# Si5395_CLK_GEN.net
KiCad netlist of a schematic drawn in Altium Designer
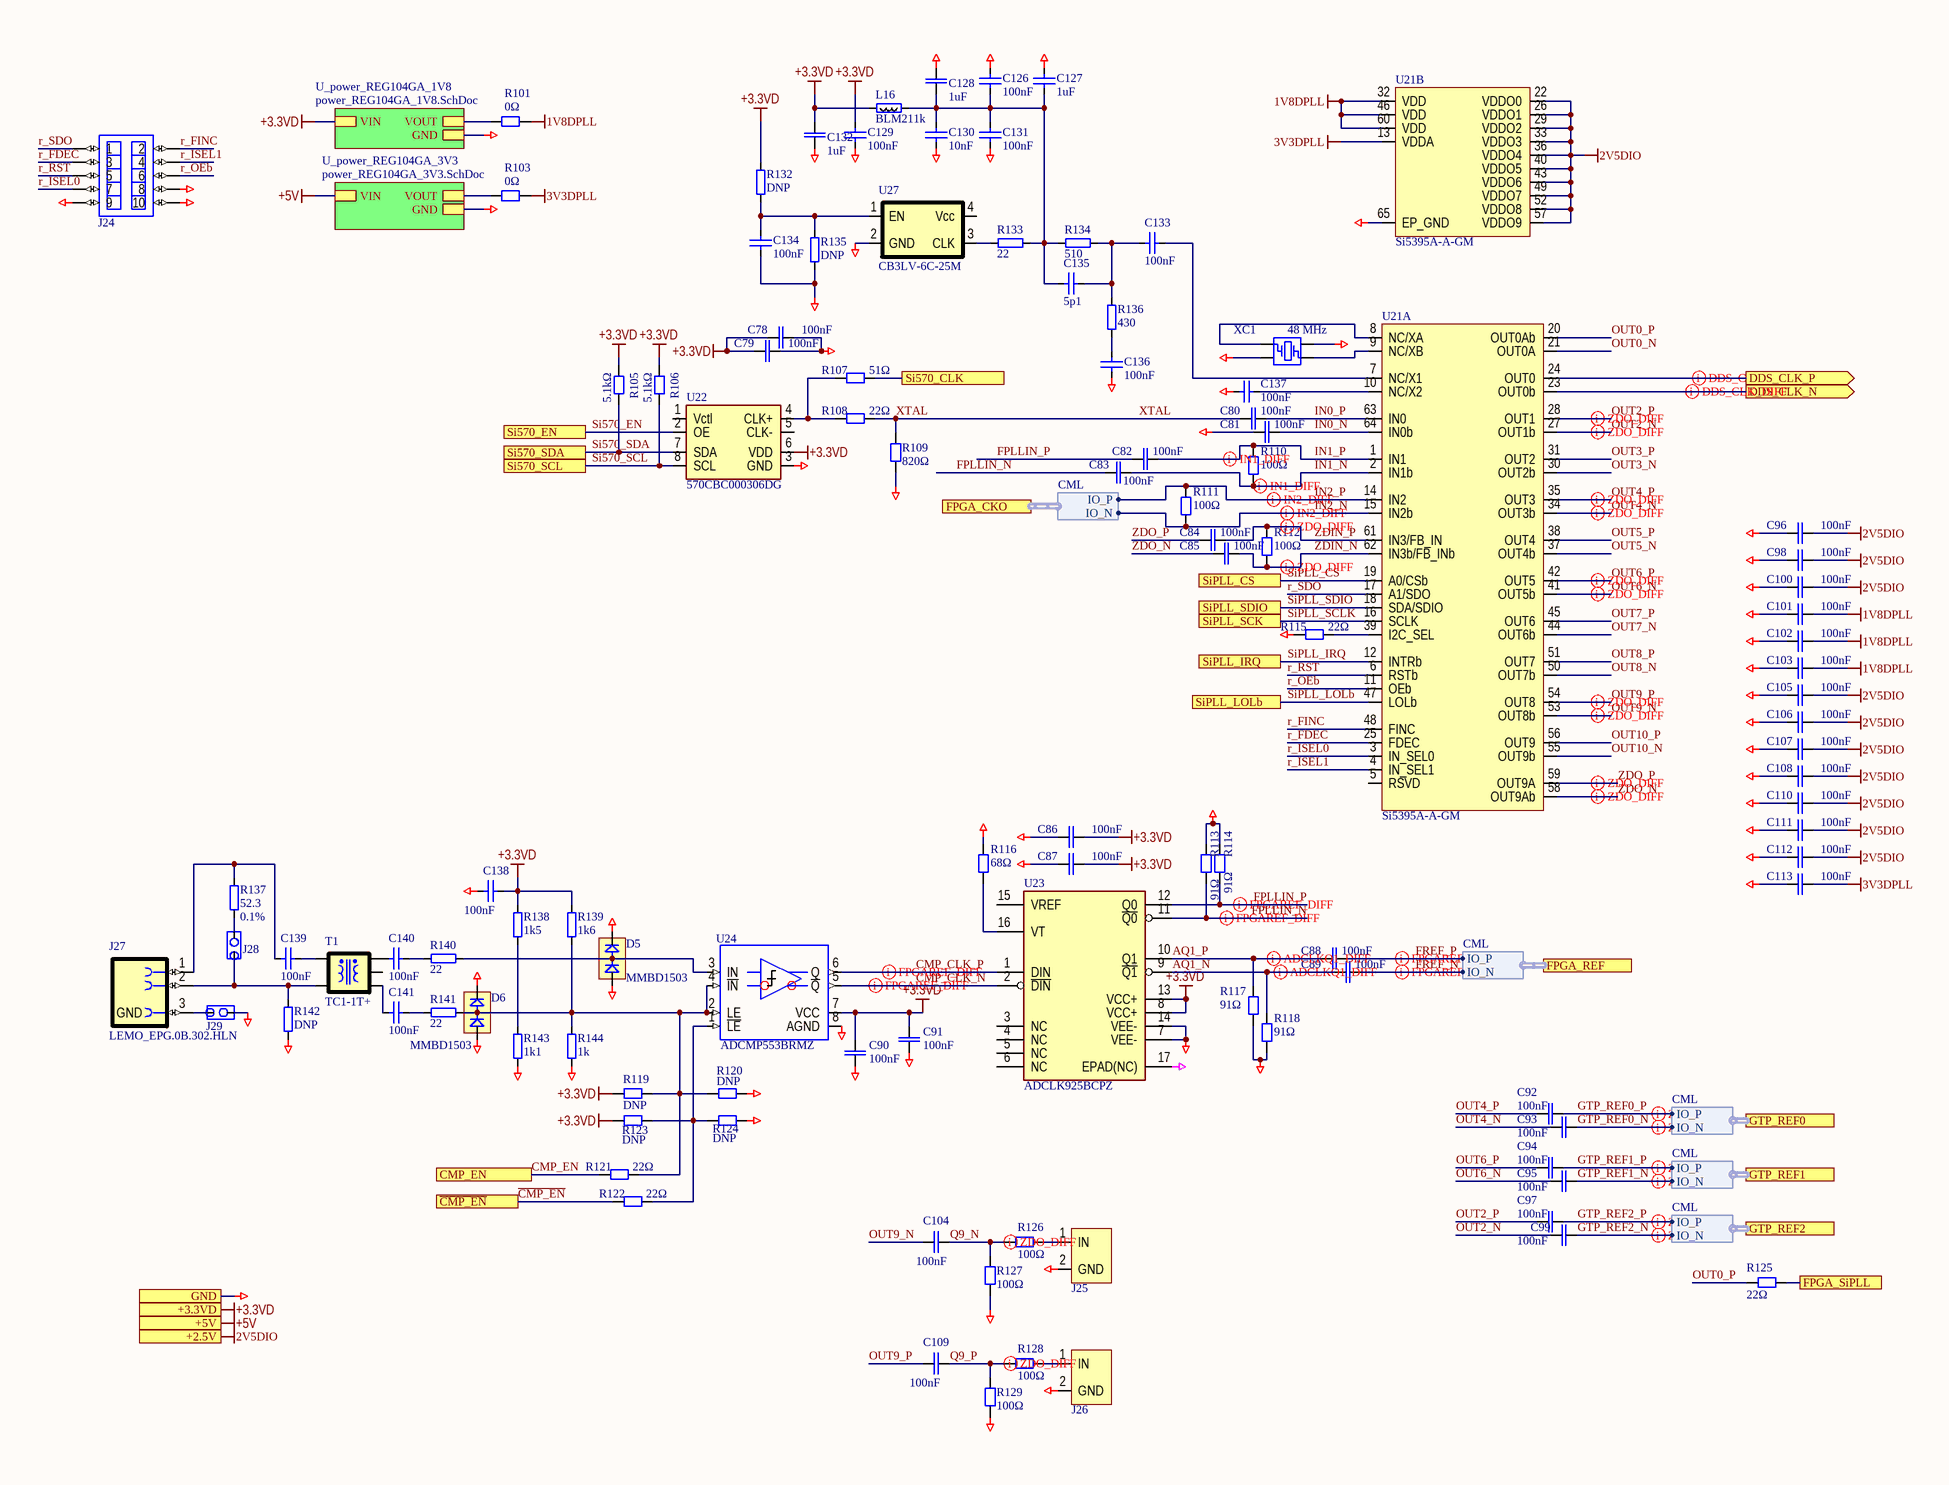
[diagram p0: Si5395_CLK_GEN.SchDoc]

(export (version "E")
  (design (tool "Eeschema 10.0.6"))
  (components
    (comp (ref "C78")
      (value "100nF")
      (footprint "CAPC1608N")
      (description "Generic ceramic SMD capacitor")
      (fields (field (name "MAINTAINER") "Evgeniy Kotov"))
      (libsource (lib "carrier") (part "CAPC"))
    )
    (comp (ref "C79")
      (value "100nF")
      (footprint "CAPC1608N")
      (description "Generic ceramic SMD capacitor")
      (fields (field (name "MAINTAINER") "Evgeniy Kotov"))
      (libsource (lib "carrier") (part "CAPC"))
    )
    (comp (ref "C80")
      (value "100nF")
      (footprint "CAPC1608N")
      (description "Generic ceramic SMD capacitor")
      (fields (field (name "MAINTAINER") "Evgeniy Kotov"))
      (libsource (lib "carrier") (part "CAPC"))
    )
    (comp (ref "C81")
      (value "100nF")
      (footprint "CAPC1608N")
      (description "Generic ceramic SMD capacitor")
      (fields (field (name "MAINTAINER") "Evgeniy Kotov"))
      (libsource (lib "carrier") (part "CAPC"))
    )
    (comp (ref "C82")
      (value "100nF")
      (footprint "CAPC1608N")
      (description "Generic ceramic SMD capacitor")
      (fields (field (name "MAINTAINER") "Evgeniy Kotov"))
      (libsource (lib "carrier") (part "CAPC"))
    )
    (comp (ref "C83")
      (value "100nF")
      (footprint "CAPC1608N")
      (description "Generic ceramic SMD capacitor")
      (fields (field (name "MAINTAINER") "Evgeniy Kotov"))
      (libsource (lib "carrier") (part "CAPC"))
    )
    (comp (ref "C84")
      (value "100nF")
      (footprint "CAPC1608N")
      (description "Generic ceramic SMD capacitor")
      (fields (field (name "MAINTAINER") "Evgeniy Kotov"))
      (libsource (lib "carrier") (part "CAPC"))
    )
    (comp (ref "C85")
      (value "100nF")
      (footprint "CAPC1608N")
      (description "Generic ceramic SMD capacitor")
      (fields (field (name "MAINTAINER") "Evgeniy Kotov"))
      (libsource (lib "carrier") (part "CAPC"))
    )
    (comp (ref "C86")
      (value "100nF")
      (footprint "CAPC1608N")
      (description "Generic ceramic SMD capacitor")
      (fields (field (name "MAINTAINER") "Evgeniy Kotov"))
      (libsource (lib "carrier") (part "CAPC"))
    )
    (comp (ref "C87")
      (value "100nF")
      (footprint "CAPC1608N")
      (description "Generic ceramic SMD capacitor")
      (fields (field (name "MAINTAINER") "Evgeniy Kotov"))
      (libsource (lib "carrier") (part "CAPC"))
    )
    (comp (ref "C88")
      (value "100nF")
      (footprint "CAPC1608N")
      (description "Generic ceramic SMD capacitor")
      (fields (field (name "MAINTAINER") "Evgeniy Kotov"))
      (libsource (lib "carrier") (part "CAPC"))
    )
    (comp (ref "C89")
      (value "100nF")
      (footprint "CAPC1608N")
      (description "Generic ceramic SMD capacitor")
      (fields (field (name "MAINTAINER") "Evgeniy Kotov"))
      (libsource (lib "carrier") (part "CAPC"))
    )
    (comp (ref "C90")
      (value "100nF")
      (footprint "CAPC1608N")
      (description "Generic ceramic SMD capacitor")
      (fields (field (name "MAINTAINER") "Evgeniy Kotov"))
      (libsource (lib "carrier") (part "CAPC"))
    )
    (comp (ref "C91")
      (value "100nF")
      (footprint "CAPC1608N")
      (description "Generic ceramic SMD capacitor")
      (fields (field (name "MAINTAINER") "Evgeniy Kotov"))
      (libsource (lib "carrier") (part "CAPC"))
    )
    (comp (ref "C92")
      (value "100nF")
      (footprint "CAPC1608N")
      (description "Generic ceramic SMD capacitor")
      (fields (field (name "MAINTAINER") "Evgeniy Kotov"))
      (libsource (lib "carrier") (part "CAPC"))
    )
    (comp (ref "C93")
      (value "100nF")
      (footprint "CAPC1608N")
      (description "Generic ceramic SMD capacitor")
      (fields (field (name "MAINTAINER") "Evgeniy Kotov"))
      (libsource (lib "carrier") (part "CAPC"))
    )
    (comp (ref "C94")
      (value "100nF")
      (footprint "CAPC1608N")
      (description "Generic ceramic SMD capacitor")
      (fields (field (name "MAINTAINER") "Evgeniy Kotov"))
      (libsource (lib "carrier") (part "CAPC"))
    )
    (comp (ref "C95")
      (value "100nF")
      (footprint "CAPC1608N")
      (description "Generic ceramic SMD capacitor")
      (fields (field (name "MAINTAINER") "Evgeniy Kotov"))
      (libsource (lib "carrier") (part "CAPC"))
    )
    (comp (ref "C96")
      (value "100nF")
      (footprint "CAPC1608N")
      (description "Generic ceramic SMD capacitor")
      (fields (field (name "MAINTAINER") "Evgeniy Kotov"))
      (libsource (lib "carrier") (part "CAPC"))
    )
    (comp (ref "C97")
      (value "100nF")
      (footprint "CAPC1608N")
      (description "Generic ceramic SMD capacitor")
      (fields (field (name "MAINTAINER") "Evgeniy Kotov"))
      (libsource (lib "carrier") (part "CAPC"))
    )
    (comp (ref "C98")
      (value "100nF")
      (footprint "CAPC1608N")
      (description "Generic ceramic SMD capacitor")
      (fields (field (name "MAINTAINER") "Evgeniy Kotov"))
      (libsource (lib "carrier") (part "CAPC"))
    )
    (comp (ref "C99")
      (value "100nF")
      (footprint "CAPC1608N")
      (description "Generic ceramic SMD capacitor")
      (fields (field (name "MAINTAINER") "Evgeniy Kotov"))
      (libsource (lib "carrier") (part "CAPC"))
    )
    (comp (ref "C100")
      (value "100nF")
      (footprint "CAPC1608N")
      (description "Generic ceramic SMD capacitor")
      (fields (field (name "MAINTAINER") "Evgeniy Kotov"))
      (libsource (lib "carrier") (part "CAPC"))
    )
    (comp (ref "C101")
      (value "100nF")
      (footprint "CAPC1608N")
      (description "Generic ceramic SMD capacitor")
      (fields (field (name "MAINTAINER") "Evgeniy Kotov"))
      (libsource (lib "carrier") (part "CAPC"))
    )
    (comp (ref "C102")
      (value "100nF")
      (footprint "CAPC1608N")
      (description "Generic ceramic SMD capacitor")
      (fields (field (name "MAINTAINER") "Evgeniy Kotov"))
      (libsource (lib "carrier") (part "CAPC"))
    )
    (comp (ref "C103")
      (value "100nF")
      (footprint "CAPC1608N")
      (description "Generic ceramic SMD capacitor")
      (fields (field (name "MAINTAINER") "Evgeniy Kotov"))
      (libsource (lib "carrier") (part "CAPC"))
    )
    (comp (ref "C104")
      (value "100nF")
      (footprint "CAPC1608N")
      (description "Generic ceramic SMD capacitor")
      (fields (field (name "MAINTAINER") "Evgeniy Kotov"))
      (libsource (lib "carrier") (part "CAPC"))
    )
    (comp (ref "C105")
      (value "100nF")
      (footprint "CAPC1608N")
      (description "Generic ceramic SMD capacitor")
      (fields (field (name "MAINTAINER") "Evgeniy Kotov"))
      (libsource (lib "carrier") (part "CAPC"))
    )
    (comp (ref "C106")
      (value "100nF")
      (footprint "CAPC1608N")
      (description "Generic ceramic SMD capacitor")
      (fields (field (name "MAINTAINER") "Evgeniy Kotov"))
      (libsource (lib "carrier") (part "CAPC"))
    )
    (comp (ref "C107")
      (value "100nF")
      (footprint "CAPC1608N")
      (description "Generic ceramic SMD capacitor")
      (fields (field (name "MAINTAINER") "Evgeniy Kotov"))
      (libsource (lib "carrier") (part "CAPC"))
    )
    (comp (ref "C108")
      (value "100nF")
      (footprint "CAPC1608N")
      (description "Generic ceramic SMD capacitor")
      (fields (field (name "MAINTAINER") "Evgeniy Kotov"))
      (libsource (lib "carrier") (part "CAPC"))
    )
    (comp (ref "C109")
      (value "100nF")
      (footprint "CAPC1608N")
      (description "Generic ceramic SMD capacitor")
      (fields (field (name "MAINTAINER") "Evgeniy Kotov"))
      (libsource (lib "carrier") (part "CAPC"))
    )
    (comp (ref "C110")
      (value "100nF")
      (footprint "CAPC1608N")
      (description "Generic ceramic SMD capacitor")
      (fields (field (name "MAINTAINER") "Evgeniy Kotov"))
      (libsource (lib "carrier") (part "CAPC"))
    )
    (comp (ref "C111")
      (value "100nF")
      (footprint "CAPC1608N")
      (description "Generic ceramic SMD capacitor")
      (fields (field (name "MAINTAINER") "Evgeniy Kotov"))
      (libsource (lib "carrier") (part "CAPC"))
    )
    (comp (ref "C112")
      (value "100nF")
      (footprint "CAPC1608N")
      (description "Generic ceramic SMD capacitor")
      (fields (field (name "MAINTAINER") "Evgeniy Kotov"))
      (libsource (lib "carrier") (part "CAPC"))
    )
    (comp (ref "C113")
      (value "100nF")
      (footprint "CAPC1608N")
      (description "Generic ceramic SMD capacitor")
      (fields (field (name "MAINTAINER") "Evgeniy Kotov"))
      (libsource (lib "carrier") (part "CAPC"))
    )
    (comp (ref "C126")
      (value "100nF")
      (footprint "SMD0805CAP")
      (description "Чип конденсатор 0805")
      (fields (field (name "VOLTAGE") "25V") (field (name "TOLERANCE") "20%"))
      (libsource (lib "DDSintLib") (part "C0805"))
    )
    (comp (ref "C127")
      (value "1uF")
      (footprint "SMD0805CAP")
      (description "Чип конденсатор 0805")
      (fields (field (name "VOLTAGE") "25V") (field (name "TOLERANCE") "20%"))
      (libsource (lib "DDSintLib") (part "C0805"))
    )
    (comp (ref "C128")
      (value "1uF")
      (footprint "0508")
      (description "1uF; 10V; 0805R; X7R; Low ESL; Reverse geometry")
      (libsource (lib "ADC4X250_rev7") (part "CAP_LLL219R71A105"))
    )
    (comp (ref "C129")
      (value "100nF")
      (footprint "CAPC1608X87N")
      (description "Чип конденсатор 0603")
      (fields (field (name "VOLTAGE") "50V") (field (name "TOLERANCE") "20%"))
      (libsource (lib "DDSintLib") (part "C0603"))
    )
    (comp (ref "C130")
      (value "10nF")
      (footprint "CAPC1608X87N")
      (description "Чип конденсатор 0603")
      (fields (field (name "VOLTAGE") "50V") (field (name "TOLERANCE") "20%"))
      (libsource (lib "DDSintLib") (part "C0603"))
    )
    (comp (ref "C131")
      (value "100nF")
      (footprint "CAPC1608X87N")
      (description "Чип конденсатор 0603")
      (fields (field (name "VOLTAGE") "50V") (field (name "TOLERANCE") "20%"))
      (libsource (lib "DDSintLib") (part "C0603"))
    )
    (comp (ref "C132")
      (value "1uF")
      (footprint "0508")
      (description "1uF; 10V; 0805R; X7R; Low ESL; Reverse geometry")
      (libsource (lib "ADC4X250_rev7") (part "CAP_LLL219R71A105"))
    )
    (comp (ref "C133")
      (value "100nF")
      (footprint "CAPC1608X87N")
      (description "Чип конденсатор 0603")
      (fields (field (name "VOLTAGE") "50V") (field (name "TOLERANCE") "20%"))
      (libsource (lib "DDSintLib") (part "C0603"))
    )
    (comp (ref "C134")
      (value "100nF")
      (footprint "CAPC1608X87N")
      (description "Чип конденсатор 0603")
      (fields (field (name "VOLTAGE") "50V") (field (name "TOLERANCE") "20%"))
      (libsource (lib "DDSintLib") (part "C0603"))
    )
    (comp (ref "C135")
      (value "5p1")
      (footprint "CAPC1608X87N")
      (description "Чип конденсатор 0603")
      (fields (field (name "VOLTAGE") "50V") (field (name "TOLERANCE") "20%"))
      (libsource (lib "DDSintLib") (part "C0603"))
    )
    (comp (ref "C136")
      (value "100nF")
      (footprint "CAPC1608X87N")
      (description "Чип конденсатор 0603")
      (fields (field (name "VOLTAGE") "50V") (field (name "TOLERANCE") "20%"))
      (libsource (lib "DDSintLib") (part "C0603"))
    )
    (comp (ref "C137")
      (value "100nF")
      (footprint "CAPC1608X87N")
      (description "Чип конденсатор 0603")
      (fields (field (name "VOLTAGE") "50V") (field (name "TOLERANCE") "20%"))
      (libsource (lib "DDSintLib") (part "C0603"))
    )
    (comp (ref "C138")
      (value "100nF")
      (footprint "SMD0805CAP")
      (description "Чип конденсатор 0805")
      (fields (field (name "VOLTAGE") "50V") (field (name "TOLERANCE") "20%"))
      (libsource (lib "DDSintLib") (part "C0805"))
    )
    (comp (ref "C139")
      (value "100nF")
      (footprint "SMD0805CAP")
      (description "Чип конденсатор 0805")
      (fields (field (name "VOLTAGE") "50V") (field (name "TOLERANCE") "20%"))
      (libsource (lib "DDSintLib") (part "C0805"))
    )
    (comp (ref "C140")
      (value "100nF")
      (footprint "SMD0805CAP")
      (description "Чип конденсатор 0805")
      (fields (field (name "VOLTAGE") "50V") (field (name "TOLERANCE") "20%"))
      (libsource (lib "DDSintLib") (part "C0805"))
    )
    (comp (ref "C141")
      (value "100nF")
      (footprint "SMD0805CAP")
      (description "Чип конденсатор 0805")
      (fields (field (name "VOLTAGE") "50V") (field (name "TOLERANCE") "20%"))
      (libsource (lib "DDSintLib") (part "C0805"))
    )
    (comp (ref "D5")
      (value "MMBD1503")
      (footprint "SOT95P280X115-3N")
      (description "High Conductance Low Leakage Diode")
      (libsource (lib "Cyc5_Carier") (part "MMBD1503"))
    )
    (comp (ref "D6")
      (value "MMBD1503")
      (footprint "SOT95P280X115-3N")
      (description "High Conductance Low Leakage Diode")
      (libsource (lib "Cyc5_Carier") (part "MMBD1503"))
    )
    (comp (ref "J24")
      (value "DNP")
      (footprint "PLD-10")
      (description "Connector, 5x2, Male, 2.54mm Pitch, Strait contacts, with Body")
      (fields (field (name "MAINTAINER") "Evgeniy Kotov"))
      (libsource (lib "carrier") (part "IDC-10MS"))
    )
    (comp (ref "J25")
      (value "DNP")
      (footprint "LEMO_EPA.00.250.NTN")
      (libsource (lib "carrier") (part "LEMO_EPA.00.250"))
    )
    (comp (ref "J26")
      (value "DNP")
      (footprint "LEMO_EPA.00.250.NTN")
      (libsource (lib "carrier") (part "LEMO_EPA.00.250"))
    )
    (comp (ref "J27")
      (value "LEMO_EPG.0B.302.HLN")
      (footprint "LEMO_EPG.0B.302.HLN")
      (description "LEMO дифференциальный, угдовой")
      (libsource (lib "DDSintLib") (part "LEMO_EPG.0B.302.HLN"))
    )
    (comp (ref "J28")
      (value "PLS-2")
      (footprint "PLS-2")
      (description "Connector, 5x2, Male, 2.54mm Pitch, Right Angle")
      (fields (field (name "MAINTAINER") "Evgeniy Kotov"))
      (libsource (lib "[Connectors] Miscellaneous") (part "PLS-2"))
    )
    (comp (ref "J29")
      (value "PLS-2")
      (footprint "PLS-2")
      (description "Connector, 5x2, Male, 2.54mm Pitch, Right Angle")
      (fields (field (name "MAINTAINER") "Evgeniy Kotov"))
      (libsource (lib "[Connectors] Miscellaneous") (part "PLS-2"))
    )
    (comp (ref "L16")
      (value "BLM211k")
      (footprint "RESC2012X50N")
      (description "SMD Ferrite bead 0805")
      (libsource (lib "DDSintLib") (part "BLM21"))
    )
    (comp (ref "R101")
      (value "0Ω")
      (footprint "RESC2012N")
      (description "Resistor, Generic, SMD")
      (fields (field (name "MAINTAINER") "Evgeniy Kotov"))
      (libsource (lib "carrier") (part "RESC"))
    )
    (comp (ref "R103")
      (value "0Ω")
      (footprint "RESC2012N")
      (description "Resistor, Generic, SMD")
      (fields (field (name "MAINTAINER") "Evgeniy Kotov"))
      (libsource (lib "carrier") (part "RESC"))
    )
    (comp (ref "R105")
      (value "5.1kΩ")
      (footprint "RESC2012N")
      (description "Resistor, Generic, SMD")
      (fields (field (name "MAINTAINER") "Evgeniy Kotov"))
      (libsource (lib "carrier") (part "RESC"))
    )
    (comp (ref "R106")
      (value "5.1kΩ")
      (footprint "RESC2012N")
      (description "Resistor, Generic, SMD")
      (fields (field (name "MAINTAINER") "Evgeniy Kotov"))
      (libsource (lib "carrier") (part "RESC"))
    )
    (comp (ref "R107")
      (value "51Ω")
      (footprint "RESC2012N")
      (description "Resistor, Generic, SMD")
      (fields (field (name "MAINTAINER") "Evgeniy Kotov"))
      (libsource (lib "carrier") (part "RESC"))
    )
    (comp (ref "R108")
      (value "22Ω")
      (footprint "RESC1608N")
      (description "Resistor, Generic, SMD")
      (fields (field (name "MAINTAINER") "Evgeniy Kotov"))
      (libsource (lib "carrier") (part "RESC"))
    )
    (comp (ref "R109")
      (value "820Ω")
      (footprint "RESC1608N")
      (description "Resistor, Generic, SMD")
      (fields (field (name "MAINTAINER") "Evgeniy Kotov"))
      (libsource (lib "carrier") (part "RESC"))
    )
    (comp (ref "R110")
      (value "100Ω")
      (footprint "RESC1608N")
      (description "Resistor, Generic, SMD")
      (fields (field (name "MAINTAINER") "Evgeniy Kotov"))
      (libsource (lib "carrier") (part "RESC"))
    )
    (comp (ref "R111")
      (value "100Ω")
      (footprint "RESC1608N")
      (description "Resistor, Generic, SMD")
      (fields (field (name "MAINTAINER") "Evgeniy Kotov"))
      (libsource (lib "carrier") (part "RESC"))
    )
    (comp (ref "R112")
      (value "100Ω")
      (footprint "RESC1608N")
      (description "Resistor, Generic, SMD")
      (fields (field (name "MAINTAINER") "Evgeniy Kotov"))
      (libsource (lib "carrier") (part "RESC"))
    )
    (comp (ref "R113")
      (value "91Ω")
      (footprint "RESC1608N")
      (description "Resistor, Generic, SMD")
      (fields (field (name "MAINTAINER") "Evgeniy Kotov"))
      (libsource (lib "carrier") (part "RESC"))
    )
    (comp (ref "R114")
      (value "91Ω")
      (footprint "RESC1608N")
      (description "Resistor, Generic, SMD")
      (fields (field (name "MAINTAINER") "Evgeniy Kotov"))
      (libsource (lib "carrier") (part "RESC"))
    )
    (comp (ref "R115")
      (value "22Ω")
      (footprint "RESC1608N")
      (description "Resistor, Generic, SMD")
      (fields (field (name "MAINTAINER") "Evgeniy Kotov"))
      (libsource (lib "carrier") (part "RESC"))
    )
    (comp (ref "R116")
      (value "68Ω")
      (footprint "RESC1608N")
      (description "Resistor, Generic, SMD")
      (fields (field (name "MAINTAINER") "Evgeniy Kotov"))
      (libsource (lib "carrier") (part "RESC"))
    )
    (comp (ref "R117")
      (value "91Ω")
      (footprint "RESC1608N")
      (description "Resistor, Generic, SMD")
      (fields (field (name "MAINTAINER") "Evgeniy Kotov"))
      (libsource (lib "carrier") (part "RESC"))
    )
    (comp (ref "R118")
      (value "91Ω")
      (footprint "RESC1608N")
      (description "Resistor, Generic, SMD")
      (fields (field (name "MAINTAINER") "Evgeniy Kotov"))
      (libsource (lib "carrier") (part "RESC"))
    )
    (comp (ref "R119")
      (value "DNP")
      (footprint "RESC1608N")
      (description "Resistor, Generic, SMD")
      (fields (field (name "MAINTAINER") "Evgeniy Kotov"))
      (libsource (lib "carrier") (part "RESC"))
    )
    (comp (ref "R120")
      (value "DNP")
      (footprint "RESC1608N")
      (description "Resistor, Generic, SMD")
      (fields (field (name "MAINTAINER") "Evgeniy Kotov"))
      (libsource (lib "carrier") (part "RESC"))
    )
    (comp (ref "R121")
      (value "22Ω")
      (footprint "RESC1608N")
      (description "Resistor, Generic, SMD")
      (fields (field (name "MAINTAINER") "Evgeniy Kotov"))
      (libsource (lib "carrier") (part "RESC"))
    )
    (comp (ref "R122")
      (value "22Ω")
      (footprint "RESC1608N")
      (description "Resistor, Generic, SMD")
      (fields (field (name "MAINTAINER") "Evgeniy Kotov"))
      (libsource (lib "carrier") (part "RESC"))
    )
    (comp (ref "R123")
      (value "DNP")
      (footprint "RESC1608N")
      (description "Resistor, Generic, SMD")
      (fields (field (name "MAINTAINER") "Evgeniy Kotov"))
      (libsource (lib "carrier") (part "RESC"))
    )
    (comp (ref "R124")
      (value "DNP")
      (footprint "RESC1608N")
      (description "Resistor, Generic, SMD")
      (fields (field (name "MAINTAINER") "Evgeniy Kotov"))
      (libsource (lib "carrier") (part "RESC"))
    )
    (comp (ref "R125")
      (value "22Ω")
      (footprint "RESC1608N")
      (description "Resistor, Generic, SMD")
      (fields (field (name "MAINTAINER") "Evgeniy Kotov"))
      (libsource (lib "carrier") (part "RESC"))
    )
    (comp (ref "R126")
      (value "100Ω")
      (footprint "RESC1608N")
      (description "Resistor, Generic, SMD")
      (fields (field (name "MAINTAINER") "Evgeniy Kotov"))
      (libsource (lib "carrier") (part "RESC"))
    )
    (comp (ref "R127")
      (value "100Ω")
      (footprint "RESC1608N")
      (description "Resistor, Generic, SMD")
      (fields (field (name "MAINTAINER") "Evgeniy Kotov"))
      (libsource (lib "carrier") (part "RESC"))
    )
    (comp (ref "R128")
      (value "100Ω")
      (footprint "RESC1608N")
      (description "Resistor, Generic, SMD")
      (fields (field (name "MAINTAINER") "Evgeniy Kotov"))
      (libsource (lib "carrier") (part "RESC"))
    )
    (comp (ref "R129")
      (value "100Ω")
      (footprint "RESC1608N")
      (description "Resistor, Generic, SMD")
      (fields (field (name "MAINTAINER") "Evgeniy Kotov"))
      (libsource (lib "carrier") (part "RESC"))
    )
    (comp (ref "R132")
      (value "DNP")
      (footprint "SMD0805RES")
      (description "Чип резистор 0805")
      (fields (field (name "TOLERANCE") "1%"))
      (libsource (lib "DDSintLib") (part "R0805"))
    )
    (comp (ref "R133")
      (value "22")
      (footprint "SMD0805RES")
      (description "Чип резистор 0805")
      (fields (field (name "TOLERANCE") "1%"))
      (libsource (lib "DDSintLib") (part "R0805"))
    )
    (comp (ref "R134")
      (value "510")
      (footprint "SMD0805RES")
      (description "Чип резистор 0805")
      (fields (field (name "TOLERANCE") "1%"))
      (libsource (lib "DDSintLib") (part "R0805"))
    )
    (comp (ref "R135")
      (value "DNP")
      (footprint "SMD0805RES")
      (description "Чип резистор 0805")
      (fields (field (name "TOLERANCE") "1%"))
      (libsource (lib "DDSintLib") (part "R0805"))
    )
    (comp (ref "R136")
      (value "430")
      (footprint "SMD0805RES")
      (description "Чип резистор 0805")
      (fields (field (name "TOLERANCE") "1%"))
      (libsource (lib "DDSintLib") (part "R0805"))
    )
    (comp (ref "R137")
      (value "52.3")
      (footprint "SMD0805RES")
      (description "Чип резистор 0805")
      (fields (field (name "TOLERANCE") "0.1%"))
      (libsource (lib "DDSintLib") (part "R0805"))
    )
    (comp (ref "R138")
      (value "1k5")
      (footprint "SMD0805RES")
      (description "Чип резистор 0805")
      (fields (field (name "TOLERANCE") "1%"))
      (libsource (lib "DDSintLib") (part "R0805"))
    )
    (comp (ref "R139")
      (value "1k6")
      (footprint "SMD0805RES")
      (description "Чип резистор 0805")
      (fields (field (name "TOLERANCE") "1%"))
      (libsource (lib "DDSintLib") (part "R0805"))
    )
    (comp (ref "R140")
      (value "22")
      (footprint "SMD0805RES")
      (description "Чип резистор 0805")
      (fields (field (name "TOLERANCE") "1%"))
      (libsource (lib "DDSintLib") (part "R0805"))
    )
    (comp (ref "R141")
      (value "22")
      (footprint "SMD0805RES")
      (description "Чип резистор 0805")
      (fields (field (name "TOLERANCE") "1%"))
      (libsource (lib "DDSintLib") (part "R0805"))
    )
    (comp (ref "R142")
      (value "DNP")
      (footprint "SMD0805RES")
      (description "Чип резистор 0805")
      (fields (field (name "TOLERANCE") "1%"))
      (libsource (lib "DDSintLib") (part "R0805"))
    )
    (comp (ref "R143")
      (value "1k1")
      (footprint "SMD0805RES")
      (description "Чип резистор 0805")
      (fields (field (name "TOLERANCE") "1%"))
      (libsource (lib "DDSintLib") (part "R0805"))
    )
    (comp (ref "R144")
      (value "1k")
      (footprint "SMD0805RES")
      (description "Чип резистор 0805")
      (fields (field (name "TOLERANCE") "1%"))
      (libsource (lib "DDSintLib") (part "R0805"))
    )
    (comp (ref "T1")
      (value "TC1-1T+")
      (footprint "XFMR_MINI-CIRCUITS_AT224")
      (description "RF Transformer; 50Ω; 1.5 to 500 MHz; Impedance Ratio=1")
      (libsource (lib "DDSintLib") (part "TC1-1T+"))
    )
    (comp (ref "U21")
      (value "Si5395A-A-GM")
      (footprint "QFN50P900X900X100-65N-S530")
      (fields (field (name "MANUFACTURER") "SiLabs"))
      (libsource (lib "carrier") (part "Si5395A"))
    )
    (comp (ref "U22")
      (value "570CBC000306DG")
      (footprint "FP-57x-MFG")
      (description "XTAL OSCILLATOR SMD")
      (fields
        (field (name "MANUFACTURER") "Silicon Labs")
        (field (name "OCTOPART") "https://octopart.com/541aaa001040bagr-silicon+labs-103392146")
        (field (name "MAINTAINER") "Evgeniy Kotov")
      )
      (libsource (lib "carrier") (part "Si570"))
    )
    (comp (ref "U23")
      (value "ADCLK925BCPZ")
      (footprint "QFN50P300X300X100-17N-S150")
      (description "IC CLK FANOUT BUFFER 1:2 16LFCSP")
      (fields
        (field (name "OCTOPART") "https://octopart.com/si53307-b-gm-silicon+labs-51374320")
        (field (name "MANUFACTURER") "Silicon Labs")
        (field (name "MAINTAINER") "Evgeniy Kotov")
      )
      (libsource (lib "carrier") (part "ADCLK925BCPZ"))
    )
    (comp (ref "U24")
      (value "ADCMP553BRMZ")
      (footprint "SOP65P490X110-8N")
      (description "LVDS Comparator")
      (libsource (lib "carrier") (part "ADCMP553BRMZ"))
    )
    (comp (ref "U27")
      (value "CB3LV-6C-25M")
      (footprint "OSCSC508P500X700X160-4N")
      (description "Clock generator")
      (libsource (lib "DDSintLib") (part "CB3LV"))
    )
    (comp (ref "XC1")
      (value "48 MHz")
      (footprint "SMD3225_4PIN_XTAL")
      (description "Kyocera XTAL 48MHz CX3225SB48000D0WPSC1")
      (fields (field (name "Comment") "CX3225SB48000D0WPSC1") (field (name "MAINTAINER") "Evgeniy Kotov"))
      (libsource (lib "carrier") (part "XTAL_CX3225SB48"))
    )
  )
  (nets
    (net (code "2") (name "+3.3VD") (class "Default")
      (node (ref "C129") (pin "2") (pinfunction "2_2") (pintype "passive"))
      (node (ref "C132") (pin "1") (pintype "passive"))
      (node (ref "C138") (pin "1") (pinfunction "1_1") (pintype "passive"))
      (node (ref "C78") (pin "1") (pintype "passive"))
      (node (ref "C79") (pin "1") (pintype "passive"))
      (node (ref "C86") (pin "2") (pintype "passive"))
      (node (ref "C87") (pin "2") (pintype "passive"))
      (node (ref "C90") (pin "1") (pintype "passive"))
      (node (ref "C91") (pin "1") (pintype "passive"))
      (node (ref "L16") (pin "1") (pinfunction "1_1") (pintype "passive"))
      (node (ref "R105") (pin "1") (pintype "passive"))
      (node (ref "R106") (pin "1") (pintype "passive"))
      (node (ref "R119") (pin "1") (pintype "passive"))
      (node (ref "R123") (pin "1") (pintype "passive"))
      (node (ref "R132") (pin "2") (pinfunction "2_2") (pintype "passive"))
      (node (ref "R138") (pin "2") (pinfunction "2_2") (pintype "passive"))
      (node (ref "R139") (pin "2") (pinfunction "2_2") (pintype "passive"))
      (node (ref "U22") (pin "6") (pinfunction "VDD_6") (pintype "power_in"))
      (node (ref "U23") (pin "13") (pinfunction "VCC+_13") (pintype "passive"))
      (node (ref "U23") (pin "8") (pinfunction "VCC+_8") (pintype "power_in"))
      (node (ref "U24") (pin "7") (pinfunction "VCC_7") (pintype "power_in"))
    )
    (net (code "4") (name "/AQ1_N") (class "Default")
      (node (ref "C89") (pin "1") (pintype "passive"))
      (node (ref "R118") (pin "2") (pintype "passive"))
      (node (ref "U23") (pin "9") (pinfunction "~{Q1}_9") (pintype "passive"))
    )
    (net (code "5") (name "/AQ1_P") (class "Default")
      (node (ref "C88") (pin "1") (pintype "passive"))
      (node (ref "R117") (pin "2") (pintype "passive"))
      (node (ref "U23") (pin "10") (pinfunction "Q1_10") (pintype "passive"))
    )
    (net (code "6") (name "/CMP_CLK_N") (class "Default")
      (node (ref "U23") (pin "2") (pinfunction "~{DIN}_2") (pintype "passive"))
      (node (ref "U24") (pin "5") (pinfunction "~{Q}_5") (pintype "output"))
    )
    (net (code "7") (name "/CMP_CLK_P") (class "Default")
      (node (ref "U23") (pin "1") (pinfunction "DIN_1") (pintype "passive"))
      (node (ref "U24") (pin "6") (pinfunction "Q_6") (pintype "output"))
    )
    (net (code "8") (name "/CMP_EN") (class "Default") (node (ref "R121") (pin "1") (pintype "passive")))
    (net (code "9") (name "/DDS_CLK_N") (class "Default")
      (node (ref "U21") (pin "23") (pinfunction "OUT0b_23") (pintype "passive"))
    )
    (net (code "10") (name "/DDS_CLK_P") (class "Default")
      (node (ref "U21") (pin "24") (pinfunction "OUT0_24") (pintype "passive"))
    )
    (net (code "11") (name "/FPGA_SiPLL") (class "Default") (node (ref "R125") (pin "2") (pintype "passive")))
    (net (code "12") (name "/FPLLIN_N") (class "Default")
      (node (ref "C83") (pin "1") (pintype "passive"))
      (node (ref "R113") (pin "1") (pintype "passive"))
      (node (ref "U23") (pin "11") (pinfunction "~{Q0}_11") (pintype "passive"))
    )
    (net (code "13") (name "/FPLLIN_P") (class "Default")
      (node (ref "C82") (pin "1") (pintype "passive"))
      (node (ref "R114") (pin "1") (pintype "passive"))
      (node (ref "U23") (pin "12") (pinfunction "Q0_12") (pintype "passive"))
    )
    (net (code "14") (name "/FREF_N") (class "Default") (node (ref "C89") (pin "2") (pintype "passive")))
    (net (code "15") (name "/FREF_P") (class "Default") (node (ref "C88") (pin "2") (pintype "passive")))
    (net (code "16") (name "/GTP_REF0_N") (class "Default") (node (ref "C93") (pin "2") (pintype "passive")))
    (net (code "17") (name "/GTP_REF0_P") (class "Default") (node (ref "C92") (pin "2") (pintype "passive")))
    (net (code "18") (name "/GTP_REF1_N") (class "Default") (node (ref "C95") (pin "2") (pintype "passive")))
    (net (code "19") (name "/GTP_REF1_P") (class "Default") (node (ref "C94") (pin "2") (pintype "passive")))
    (net (code "20") (name "/GTP_REF2_N") (class "Default") (node (ref "C99") (pin "2") (pintype "passive")))
    (net (code "21") (name "/GTP_REF2_P") (class "Default") (node (ref "C97") (pin "2") (pintype "passive")))
    (net (code "22") (name "/IN0_N") (class "Default")
      (node (ref "C81") (pin "2") (pintype "passive"))
      (node (ref "U21") (pin "64") (pinfunction "IN0b_64") (pintype "passive"))
    )
    (net (code "23") (name "/IN0_P") (class "Default")
      (node (ref "C80") (pin "2") (pintype "passive"))
      (node (ref "U21") (pin "63") (pinfunction "IN0_63") (pintype "passive"))
    )
    (net (code "24") (name "/IN1_N") (class "Default")
      (node (ref "C83") (pin "2") (pintype "passive"))
      (node (ref "R110") (pin "1") (pintype "passive"))
      (node (ref "U21") (pin "2") (pinfunction "IN1b_2") (pintype "passive"))
    )
    (net (code "25") (name "/IN1_P") (class "Default")
      (node (ref "C82") (pin "2") (pintype "passive"))
      (node (ref "R110") (pin "2") (pintype "passive"))
      (node (ref "U21") (pin "1") (pinfunction "IN1_1") (pintype "passive"))
    )
    (net (code "26") (name "/IN2_N") (class "Default")
      (node (ref "R111") (pin "1") (pintype "passive"))
      (node (ref "U21") (pin "15") (pinfunction "IN2b_15") (pintype "passive"))
    )
    (net (code "27") (name "/IN2_P") (class "Default")
      (node (ref "R111") (pin "2") (pintype "passive"))
      (node (ref "U21") (pin "14") (pinfunction "IN2_14") (pintype "passive"))
    )
    (net (code "28") (name "/OUT0_N") (class "Default")
      (node (ref "U21") (pin "21") (pinfunction "OUT0A_21") (pintype "passive"))
    )
    (net (code "29") (name "/OUT0_P") (class "Default")
      (node (ref "R125") (pin "1") (pintype "passive"))
      (node (ref "U21") (pin "20") (pinfunction "OUT0Ab_20") (pintype "passive"))
    )
    (net (code "30") (name "/OUT2_N") (class "Default")
      (node (ref "C99") (pin "1") (pintype "passive"))
      (node (ref "U21") (pin "27") (pinfunction "OUT1b_27") (pintype "passive"))
    )
    (net (code "31") (name "/OUT2_P") (class "Default")
      (node (ref "C97") (pin "1") (pintype "passive"))
      (node (ref "U21") (pin "28") (pinfunction "OUT1_28") (pintype "passive"))
    )
    (net (code "32") (name "/OUT3_N") (class "Default")
      (node (ref "U21") (pin "30") (pinfunction "OUT2b_30") (pintype "passive"))
    )
    (net (code "33") (name "/OUT3_P") (class "Default")
      (node (ref "U21") (pin "31") (pinfunction "OUT2_31") (pintype "passive"))
    )
    (net (code "34") (name "/OUT4_N") (class "Default")
      (node (ref "C93") (pin "1") (pintype "passive"))
      (node (ref "U21") (pin "34") (pinfunction "OUT3b_34") (pintype "passive"))
    )
    (net (code "35") (name "/OUT4_P") (class "Default")
      (node (ref "C92") (pin "1") (pintype "passive"))
      (node (ref "U21") (pin "35") (pinfunction "OUT3_35") (pintype "passive"))
    )
    (net (code "36") (name "/OUT5_N") (class "Default")
      (node (ref "U21") (pin "37") (pinfunction "OUT4b_37") (pintype "passive"))
    )
    (net (code "37") (name "/OUT5_P") (class "Default")
      (node (ref "U21") (pin "38") (pinfunction "OUT4_38") (pintype "passive"))
    )
    (net (code "38") (name "/OUT6_N") (class "Default")
      (node (ref "C95") (pin "1") (pintype "passive"))
      (node (ref "U21") (pin "41") (pinfunction "OUT5b_41") (pintype "passive"))
    )
    (net (code "39") (name "/OUT6_P") (class "Default")
      (node (ref "C94") (pin "1") (pintype "passive"))
      (node (ref "U21") (pin "42") (pinfunction "OUT5_42") (pintype "passive"))
    )
    (net (code "40") (name "/OUT7_N") (class "Default")
      (node (ref "U21") (pin "44") (pinfunction "OUT6b_44") (pintype "passive"))
    )
    (net (code "41") (name "/OUT7_P") (class "Default")
      (node (ref "U21") (pin "45") (pinfunction "OUT6_45") (pintype "passive"))
    )
    (net (code "42") (name "/OUT8_N") (class "Default")
      (node (ref "U21") (pin "50") (pinfunction "OUT7b_50") (pintype "passive"))
    )
    (net (code "43") (name "/OUT8_P") (class "Default")
      (node (ref "U21") (pin "51") (pinfunction "OUT7_51") (pintype "passive"))
    )
    (net (code "44") (name "/OUT9_N") (class "Default")
      (node (ref "C104") (pin "1") (pintype "passive"))
      (node (ref "U21") (pin "53") (pinfunction "OUT8b_53") (pintype "passive"))
    )
    (net (code "45") (name "/OUT9_P") (class "Default")
      (node (ref "C109") (pin "1") (pintype "passive"))
      (node (ref "U21") (pin "54") (pinfunction "OUT8_54") (pintype "passive"))
    )
    (net (code "46") (name "/OUT10_N") (class "Default")
      (node (ref "U21") (pin "55") (pinfunction "OUT9b_55") (pintype "passive"))
    )
    (net (code "47") (name "/OUT10_P") (class "Default")
      (node (ref "U21") (pin "56") (pinfunction "OUT9_56") (pintype "passive"))
    )
    (net (code "48") (name "/Q9_N") (class "Default")
      (node (ref "C104") (pin "2") (pintype "passive"))
      (node (ref "R126") (pin "1") (pintype "passive"))
      (node (ref "R127") (pin "2") (pintype "passive"))
    )
    (net (code "49") (name "/Q9_P") (class "Default")
      (node (ref "C109") (pin "2") (pintype "passive"))
      (node (ref "R128") (pin "1") (pintype "passive"))
      (node (ref "R129") (pin "2") (pintype "passive"))
    )
    (net (code "50") (name "/Si570_CLK") (class "Default") (node (ref "R107") (pin "2") (pintype "passive")))
    (net (code "51") (name "/Si570_EN") (class "Default")
      (node (ref "U22") (pin "2") (pinfunction "OE_2") (pintype "passive"))
    )
    (net (code "52") (name "/Si570_SCL") (class "Default")
      (node (ref "R106") (pin "2") (pintype "passive"))
      (node (ref "U22") (pin "8") (pinfunction "SCL_8") (pintype "power_in"))
    )
    (net (code "53") (name "/Si570_SDA") (class "Default")
      (node (ref "R105") (pin "2") (pintype "passive"))
      (node (ref "U22") (pin "7") (pinfunction "SDA_7") (pintype "power_in"))
    )
    (net (code "54") (name "/SiPLL_CS") (class "Default")
      (node (ref "U21") (pin "19") (pinfunction "A0/CSb_19") (pintype "passive"))
    )
    (net (code "55") (name "/SiPLL_IRQ") (class "Default")
      (node (ref "U21") (pin "12") (pinfunction "INTRb_12") (pintype "passive"))
    )
    (net (code "56") (name "/SiPLL_LOLb") (class "Default")
      (node (ref "U21") (pin "47") (pinfunction "LOLb_47") (pintype "passive"))
    )
    (net (code "57") (name "/SiPLL_SCLK") (class "Default")
      (node (ref "U21") (pin "16") (pinfunction "SCLK_16") (pintype "passive"))
    )
    (net (code "58") (name "/SiPLL_SDIO") (class "Default")
      (node (ref "U21") (pin "18") (pinfunction "SDA/SDIO_18") (pintype "passive"))
    )
    (net (code "59") (name "/VOUT") (class "Default") (node (ref "R101") (pin "2") (pintype "passive")))
    (net (code "60") (name "/VOUT_1") (class "Default") (node (ref "R103") (pin "2") (pintype "passive")))
    (net (code "61") (name "/XTAL") (class "Default")
      (node (ref "C80") (pin "1") (pintype "passive"))
      (node (ref "R108") (pin "2") (pintype "passive"))
      (node (ref "R109") (pin "1") (pintype "passive"))
    )
    (net (code "62") (name "/ZDIN_N") (class "Default")
      (node (ref "C85") (pin "2") (pintype "passive"))
      (node (ref "R112") (pin "1") (pintype "passive"))
      (node (ref "U21") (pin "62") (pinfunction "IN3b/FB_INb_62") (pintype "passive"))
    )
    (net (code "63") (name "/ZDIN_P") (class "Default")
      (node (ref "C84") (pin "2") (pintype "passive"))
      (node (ref "R112") (pin "2") (pintype "passive"))
      (node (ref "U21") (pin "61") (pinfunction "IN3/FB_IN_61") (pintype "passive"))
    )
    (net (code "64") (name "/ZDO_N") (class "Default")
      (node (ref "C85") (pin "1") (pintype "passive"))
      (node (ref "U21") (pin "58") (pinfunction "OUT9Ab_58") (pintype "passive"))
    )
    (net (code "65") (name "/ZDO_P") (class "Default")
      (node (ref "C84") (pin "1") (pintype "passive"))
      (node (ref "U21") (pin "59") (pinfunction "OUT9A_59") (pintype "passive"))
    )
    (net (code "66") (name "/r_FDEC") (class "Default")
      (node (ref "J24") (pin "3") (pinfunction "3_3") (pintype "bidirectional"))
      (node (ref "U21") (pin "25") (pinfunction "FDEC_25") (pintype "passive"))
    )
    (net (code "67") (name "/r_FINC") (class "Default")
      (node (ref "J24") (pin "2") (pinfunction "2_2") (pintype "bidirectional"))
      (node (ref "U21") (pin "48") (pinfunction "FINC_48") (pintype "passive"))
    )
    (net (code "68") (name "/r_ISEL0") (class "Default")
      (node (ref "J24") (pin "7") (pinfunction "7_7") (pintype "bidirectional"))
      (node (ref "U21") (pin "3") (pinfunction "IN_SEL0_3") (pintype "passive"))
    )
    (net (code "69") (name "/r_ISEL1") (class "Default")
      (node (ref "J24") (pin "4") (pinfunction "4_4") (pintype "bidirectional"))
      (node (ref "U21") (pin "4") (pinfunction "IN_SEL1_4") (pintype "passive"))
    )
    (net (code "70") (name "/r_OEb") (class "Default")
      (node (ref "J24") (pin "6") (pinfunction "6_6") (pintype "bidirectional"))
      (node (ref "U21") (pin "11") (pinfunction "OEb_11") (pintype "passive"))
    )
    (net (code "71") (name "/r_RST") (class "Default")
      (node (ref "J24") (pin "5") (pinfunction "5_5") (pintype "bidirectional"))
      (node (ref "U21") (pin "6") (pinfunction "RSTb_6") (pintype "passive"))
    )
    (net (code "72") (name "/r_SDO") (class "Default")
      (node (ref "J24") (pin "1") (pinfunction "1_1") (pintype "bidirectional"))
      (node (ref "U21") (pin "17") (pinfunction "A1/SDO_17") (pintype "passive"))
    )
    (net (code "74") (name "/~{CMP_EN}") (class "Default") (node (ref "R122") (pin "1") (pintype "passive")))
    (net (code "75") (name "1V8DPLL") (class "Default")
      (node (ref "C101") (pin "2") (pintype "passive"))
      (node (ref "C102") (pin "2") (pintype "passive"))
      (node (ref "C103") (pin "2") (pintype "passive"))
      (node (ref "R101") (pin "1") (pintype "passive"))
      (node (ref "U21") (pin "32") (pinfunction "VDD_32") (pintype "passive"))
      (node (ref "U21") (pin "46") (pinfunction "VDD_46") (pintype "passive"))
      (node (ref "U21") (pin "60") (pinfunction "VDD_60") (pintype "passive"))
    )
    (net (code "76") (name "2V5DIO") (class "Default")
      (node (ref "C100") (pin "2") (pintype "passive"))
      (node (ref "C105") (pin "2") (pintype "passive"))
      (node (ref "C106") (pin "2") (pintype "passive"))
      (node (ref "C107") (pin "2") (pintype "passive"))
      (node (ref "C108") (pin "2") (pintype "passive"))
      (node (ref "C110") (pin "2") (pintype "passive"))
      (node (ref "C111") (pin "2") (pintype "passive"))
      (node (ref "C112") (pin "2") (pintype "passive"))
      (node (ref "C96") (pin "2") (pintype "passive"))
      (node (ref "C98") (pin "2") (pintype "passive"))
      (node (ref "U21") (pin "22") (pinfunction "VDDO0_22") (pintype "passive"))
      (node (ref "U21") (pin "26") (pinfunction "VDDO1_26") (pintype "passive"))
      (node (ref "U21") (pin "29") (pinfunction "VDDO2_29") (pintype "passive"))
      (node (ref "U21") (pin "33") (pinfunction "VDDO3_33") (pintype "passive"))
      (node (ref "U21") (pin "36") (pinfunction "VDDO4_36") (pintype "passive"))
      (node (ref "U21") (pin "40") (pinfunction "VDDO5_40") (pintype "passive"))
      (node (ref "U21") (pin "43") (pinfunction "VDDO6_43") (pintype "passive"))
      (node (ref "U21") (pin "49") (pinfunction "VDDO7_49") (pintype "passive"))
      (node (ref "U21") (pin "52") (pinfunction "VDDO8_52") (pintype "passive"))
      (node (ref "U21") (pin "57") (pinfunction "VDDO9_57") (pintype "passive"))
    )
    (net (code "77") (name "3V3DPLL") (class "Default")
      (node (ref "C113") (pin "2") (pintype "passive"))
      (node (ref "R103") (pin "1") (pintype "passive"))
      (node (ref "U21") (pin "13") (pinfunction "VDDA_13") (pintype "passive"))
    )
    (net (code "78") (name "GEPAD") (class "Default")
      (node (ref "U23") (pin "17") (pinfunction "EPAD(NC)_17") (pintype "power_in"))
    )
    (net (code "79") (name "GND") (class "Default")
      (node (ref "C100") (pin "1") (pintype "passive"))
      (node (ref "C101") (pin "1") (pintype "passive"))
      (node (ref "C102") (pin "1") (pintype "passive"))
      (node (ref "C103") (pin "1") (pintype "passive"))
      (node (ref "C105") (pin "1") (pintype "passive"))
      (node (ref "C106") (pin "1") (pintype "passive"))
      (node (ref "C107") (pin "1") (pintype "passive"))
      (node (ref "C108") (pin "1") (pintype "passive"))
      (node (ref "C110") (pin "1") (pintype "passive"))
      (node (ref "C111") (pin "1") (pintype "passive"))
      (node (ref "C112") (pin "1") (pintype "passive"))
      (node (ref "C113") (pin "1") (pintype "passive"))
      (node (ref "C126") (pin "1") (pinfunction "1_1") (pintype "passive"))
      (node (ref "C127") (pin "1") (pinfunction "1_1") (pintype "passive"))
      (node (ref "C128") (pin "2") (pintype "passive"))
      (node (ref "C129") (pin "1") (pinfunction "1_1") (pintype "passive"))
      (node (ref "C130") (pin "1") (pinfunction "1_1") (pintype "passive"))
      (node (ref "C131") (pin "1") (pinfunction "1_1") (pintype "passive"))
      (node (ref "C132") (pin "2") (pintype "passive"))
      (node (ref "C134") (pin "1") (pinfunction "1_1") (pintype "passive"))
      (node (ref "C136") (pin "1") (pinfunction "1_1") (pintype "passive"))
      (node (ref "C137") (pin "2") (pinfunction "2_2") (pintype "passive"))
      (node (ref "C138") (pin "2") (pinfunction "2_2") (pintype "passive"))
      (node (ref "C78") (pin "2") (pintype "passive"))
      (node (ref "C79") (pin "2") (pintype "passive"))
      (node (ref "C81") (pin "1") (pintype "passive"))
      (node (ref "C86") (pin "1") (pintype "passive"))
      (node (ref "C87") (pin "1") (pintype "passive"))
      (node (ref "C90") (pin "2") (pintype "passive"))
      (node (ref "C91") (pin "2") (pintype "passive"))
      (node (ref "C96") (pin "1") (pintype "passive"))
      (node (ref "C98") (pin "1") (pintype "passive"))
      (node (ref "D5") (pin "1") (pinfunction "1_1") (pintype "passive"))
      (node (ref "D5") (pin "2") (pinfunction "2_2") (pintype "passive"))
      (node (ref "D6") (pin "1") (pinfunction "1_1") (pintype "passive"))
      (node (ref "D6") (pin "2") (pinfunction "2_2") (pintype "passive"))
      (node (ref "J24") (pin "10") (pinfunction "10_10") (pintype "bidirectional"))
      (node (ref "J24") (pin "8") (pinfunction "8_8") (pintype "bidirectional"))
      (node (ref "J24") (pin "9") (pinfunction "9_9") (pintype "bidirectional"))
      (node (ref "J25") (pin "2") (pinfunction "GND_2") (pintype "passive"))
      (node (ref "J26") (pin "2") (pinfunction "GND_2") (pintype "passive"))
      (node (ref "J29") (pin "2") (pintype "passive"))
      (node (ref "R109") (pin "2") (pintype "passive"))
      (node (ref "R113") (pin "2") (pintype "passive"))
      (node (ref "R114") (pin "2") (pintype "passive"))
      (node (ref "R115") (pin "1") (pintype "passive"))
      (node (ref "R116") (pin "2") (pintype "passive"))
      (node (ref "R117") (pin "1") (pintype "passive"))
      (node (ref "R118") (pin "1") (pintype "passive"))
      (node (ref "R120") (pin "2") (pintype "passive"))
      (node (ref "R124") (pin "2") (pintype "passive"))
      (node (ref "R127") (pin "1") (pintype "passive"))
      (node (ref "R129") (pin "1") (pintype "passive"))
      (node (ref "R135") (pin "1") (pinfunction "1_1") (pintype "passive"))
      (node (ref "R142") (pin "1") (pinfunction "1_1") (pintype "passive"))
      (node (ref "R143") (pin "1") (pinfunction "1_1") (pintype "passive"))
      (node (ref "R144") (pin "1") (pinfunction "1_1") (pintype "passive"))
      (node (ref "U21") (pin "65") (pinfunction "EP_GND_65") (pintype "passive"))
      (node (ref "U22") (pin "3") (pinfunction "GND_3") (pintype "power_in"))
      (node (ref "U23") (pin "14") (pinfunction "VEE-_14") (pintype "passive"))
      (node (ref "U23") (pin "7") (pinfunction "VEE-_7") (pintype "power_in"))
      (node (ref "U24") (pin "8") (pinfunction "AGND_8") (pintype "power_in"))
      (node (ref "U27") (pin "2") (pinfunction "GND_2") (pintype "passive"))
      (node (ref "XC1") (pin "2") (pinfunction "SLD_2") (pintype "passive"))
      (node (ref "XC1") (pin "4") (pinfunction "SLD_4") (pintype "passive"))
    )
    (net (code "80") (name "Net-(C126-Pad2)") (class "Default")
      (node (ref "C126") (pin "2") (pinfunction "2_2") (pintype "passive"))
      (node (ref "C127") (pin "2") (pinfunction "2_2") (pintype "passive"))
      (node (ref "C128") (pin "1") (pintype "passive"))
      (node (ref "C130") (pin "2") (pinfunction "2_2") (pintype "passive"))
      (node (ref "C131") (pin "2") (pinfunction "2_2") (pintype "passive"))
      (node (ref "C135") (pin "2") (pinfunction "2_2") (pintype "passive"))
      (node (ref "L16") (pin "2") (pinfunction "2_2") (pintype "passive"))
      (node (ref "R133") (pin "1") (pinfunction "1_1") (pintype "passive"))
      (node (ref "R134") (pin "2") (pinfunction "2_2") (pintype "passive"))
    )
    (net (code "81") (name "Net-(C133-Pad2)") (class "Default")
      (node (ref "C133") (pin "2") (pinfunction "2_2") (pintype "passive"))
      (node (ref "C135") (pin "1") (pinfunction "1_1") (pintype "passive"))
      (node (ref "R134") (pin "1") (pinfunction "1_1") (pintype "passive"))
      (node (ref "R136") (pin "1") (pinfunction "1_1") (pintype "passive"))
    )
    (net (code "82") (name "Net-(C136-Pad2)") (class "Default")
      (node (ref "C136") (pin "2") (pinfunction "2_2") (pintype "passive"))
      (node (ref "R136") (pin "2") (pinfunction "2_2") (pintype "passive"))
    )
    (net (code "83") (name "Net-(C139-Pad1)") (class "Default")
      (node (ref "C139") (pin "1") (pinfunction "1_1") (pintype "passive"))
      (node (ref "J27") (pin "1") (pinfunction "1_1") (pintype "bidirectional"))
      (node (ref "R137") (pin "2") (pinfunction "2_2") (pintype "passive"))
    )
    (net (code "84") (name "Net-(C139-Pad2)") (class "Default")
      (node (ref "C139") (pin "2") (pinfunction "2_2") (pintype "passive"))
      (node (ref "T1") (pin "4") (pinfunction "4_4") (pintype "passive"))
    )
    (net (code "85") (name "Net-(C140-Pad1)") (class "Default")
      (node (ref "C140") (pin "1") (pinfunction "1_1") (pintype "passive"))
      (node (ref "T1") (pin "3") (pinfunction "3_3") (pintype "passive"))
    )
    (net (code "86") (name "Net-(C140-Pad2)") (class "Default")
      (node (ref "C140") (pin "2") (pinfunction "2_2") (pintype "passive"))
      (node (ref "R140") (pin "2") (pinfunction "2_2") (pintype "passive"))
    )
    (net (code "87") (name "Net-(C141-Pad1)") (class "Default")
      (node (ref "C141") (pin "1") (pinfunction "1_1") (pintype "passive"))
      (node (ref "T1") (pin "1") (pinfunction "1_1") (pintype "passive"))
    )
    (net (code "88") (name "Net-(C141-Pad2)") (class "Default")
      (node (ref "C141") (pin "2") (pinfunction "2_2") (pintype "passive"))
      (node (ref "R141") (pin "2") (pinfunction "2_2") (pintype "passive"))
    )
    (net (code "89") (name "Net-(J25-IN)") (class "Default")
      (node (ref "J25") (pin "1") (pinfunction "IN_1") (pintype "passive"))
      (node (ref "R126") (pin "2") (pintype "passive"))
    )
    (net (code "90") (name "Net-(J26-IN)") (class "Default")
      (node (ref "J26") (pin "1") (pinfunction "IN_1") (pintype "passive"))
      (node (ref "R128") (pin "2") (pintype "passive"))
    )
    (net (code "91") (name "Net-(J27-GND)") (class "Default")
      (node (ref "J27") (pin "3") (pinfunction "GND_3") (pintype "bidirectional"))
      (node (ref "J29") (pin "1") (pintype "passive"))
    )
    (net (code "92") (name "Net-(J27-Pad2)") (class "Default")
      (node (ref "J27") (pin "2") (pinfunction "2_2") (pintype "bidirectional"))
      (node (ref "J28") (pin "1") (pintype "passive"))
      (node (ref "R142") (pin "2") (pinfunction "2_2") (pintype "passive"))
      (node (ref "T1") (pin "6") (pinfunction "6_6") (pintype "passive"))
    )
    (net (code "93") (name "Net-(J28-Pad2)") (class "Default")
      (node (ref "J28") (pin "2") (pintype "passive"))
      (node (ref "R137") (pin "1") (pinfunction "1_1") (pintype "passive"))
    )
    (net (code "94") (name "Net-(R138-Pad1)") (class "Default")
      (node (ref "R138") (pin "1") (pinfunction "1_1") (pintype "passive"))
      (node (ref "R143") (pin "2") (pinfunction "2_2") (pintype "passive"))
    )
    (net (code "95") (name "Net-(U21A-I2C_SEL)") (class "Default")
      (node (ref "R115") (pin "2") (pintype "passive"))
      (node (ref "U21") (pin "39") (pinfunction "I2C_SEL_39") (pintype "passive"))
    )
    (net (code "96") (name "Net-(U21A-NC{slash}X1)") (class "Default")
      (node (ref "C133") (pin "1") (pinfunction "1_1") (pintype "passive"))
      (node (ref "U21") (pin "7") (pinfunction "NC/X1_7") (pintype "passive"))
    )
    (net (code "97") (name "Net-(U21A-NC{slash}X2)") (class "Default")
      (node (ref "C137") (pin "1") (pinfunction "1_1") (pintype "passive"))
      (node (ref "U21") (pin "10") (pinfunction "NC/X2_10") (pintype "passive"))
    )
    (net (code "98") (name "Net-(U21A-NC{slash}XA)") (class "Default")
      (node (ref "U21") (pin "8") (pinfunction "NC/XA_8") (pintype "passive"))
      (node (ref "XC1") (pin "1") (pinfunction "XTAL+_1") (pintype "passive"))
    )
    (net (code "99") (name "Net-(U21A-NC{slash}XB)") (class "Default")
      (node (ref "U21") (pin "9") (pinfunction "NC/XB_9") (pintype "passive"))
      (node (ref "XC1") (pin "3") (pinfunction "XTAL-_3") (pintype "passive"))
    )
    (net (code "100") (name "Net-(U22-CLK+)") (class "Default")
      (node (ref "R107") (pin "1") (pintype "passive"))
      (node (ref "R108") (pin "1") (pintype "passive"))
      (node (ref "U22") (pin "4") (pinfunction "CLK+_4") (pintype "passive"))
    )
    (net (code "101") (name "Net-(U23-VT)") (class "Default")
      (node (ref "R116") (pin "1") (pintype "passive"))
      (node (ref "U23") (pin "16") (pinfunction "VT_16") (pintype "power_in"))
    )
    (net (code "102") (name "Net-(U24-IN)") (class "Default")
      (node (ref "D5") (pin "3") (pinfunction "3_3") (pintype "passive"))
      (node (ref "R140") (pin "1") (pinfunction "1_1") (pintype "passive"))
      (node (ref "U24") (pin "3") (pinfunction "IN_3") (pintype "input"))
    )
    (net (code "103") (name "Net-(U24-LE)") (class "Default")
      (node (ref "D6") (pin "3") (pinfunction "3_3") (pintype "passive"))
      (node (ref "R119") (pin "2") (pintype "passive"))
      (node (ref "R120") (pin "1") (pintype "passive"))
      (node (ref "R121") (pin "2") (pintype "passive"))
      (node (ref "R139") (pin "1") (pinfunction "1_1") (pintype "passive"))
      (node (ref "R141") (pin "1") (pinfunction "1_1") (pintype "passive"))
      (node (ref "R144") (pin "2") (pinfunction "2_2") (pintype "passive"))
      (node (ref "U24") (pin "2") (pinfunction "LE_2") (pintype "input"))
      (node (ref "U24") (pin "4") (pinfunction "~{IN}_4") (pintype "input"))
    )
    (net (code "104") (name "Net-(U24-~{LE})") (class "Default")
      (node (ref "R122") (pin "2") (pintype "passive"))
      (node (ref "R123") (pin "2") (pintype "passive"))
      (node (ref "R124") (pin "1") (pintype "passive"))
      (node (ref "U24") (pin "1") (pinfunction "~{LE}_1") (pintype "input"))
    )
    (net (code "105") (name "Net-(U27-CLK)") (class "Default")
      (node (ref "R133") (pin "2") (pinfunction "2_2") (pintype "passive"))
      (node (ref "U27") (pin "3") (pinfunction "CLK_3") (pintype "passive"))
    )
    (net (code "106") (name "Net-(U27-EN)") (class "Default")
      (node (ref "C134") (pin "2") (pinfunction "2_2") (pintype "passive"))
      (node (ref "R132") (pin "1") (pinfunction "1_1") (pintype "passive"))
      (node (ref "R135") (pin "2") (pinfunction "2_2") (pintype "passive"))
      (node (ref "U27") (pin "1") (pinfunction "EN_1") (pintype "passive"))
    )
    (net (code "107") (name "unconnected-(T1-Pad2)") (class "Default")
      (node (ref "T1") (pin "2") (pinfunction "2_2") (pintype "passive"))
    )
    (net (code "108") (name "unconnected-(U21A-RSVD-Pad5)") (class "Default")
      (node (ref "U21") (pin "5") (pinfunction "RSVD_5") (pintype "passive"))
    )
    (net (code "109") (name "unconnected-(U22-CLK--Pad5)") (class "Default")
      (node (ref "U22") (pin "5") (pinfunction "CLK-_5") (pintype "passive"))
    )
    (net (code "110") (name "unconnected-(U22-Vctl-Pad1)") (class "Default")
      (node (ref "U22") (pin "1") (pinfunction "Vctl_1") (pintype "passive"))
    )
    (net (code "111") (name "unconnected-(U23-NC-Pad3)") (class "Default")
      (node (ref "U23") (pin "3") (pinfunction "NC_3") (pintype "passive"))
    )
    (net (code "112") (name "unconnected-(U23-NC-Pad4)") (class "Default")
      (node (ref "U23") (pin "4") (pinfunction "NC_4") (pintype "passive"))
    )
    (net (code "113") (name "unconnected-(U23-NC-Pad5)") (class "Default")
      (node (ref "U23") (pin "5") (pinfunction "NC_5") (pintype "passive"))
    )
    (net (code "114") (name "unconnected-(U23-NC-Pad6)") (class "Default")
      (node (ref "U23") (pin "6") (pinfunction "NC_6") (pintype "passive"))
    )
    (net (code "115") (name "unconnected-(U23-VREF-Pad15)") (class "Default")
      (node (ref "U23") (pin "15") (pinfunction "VREF_15") (pintype "power_in"))
    )
    (net (code "116") (name "unconnected-(U27-Vcc-Pad4)") (class "Default")
      (node (ref "U27") (pin "4") (pinfunction "Vcc_4") (pintype "passive"))
    )
  )
)
